# systems_pcb.net
KiCad netlist of a schematic drawn in Altium Designer
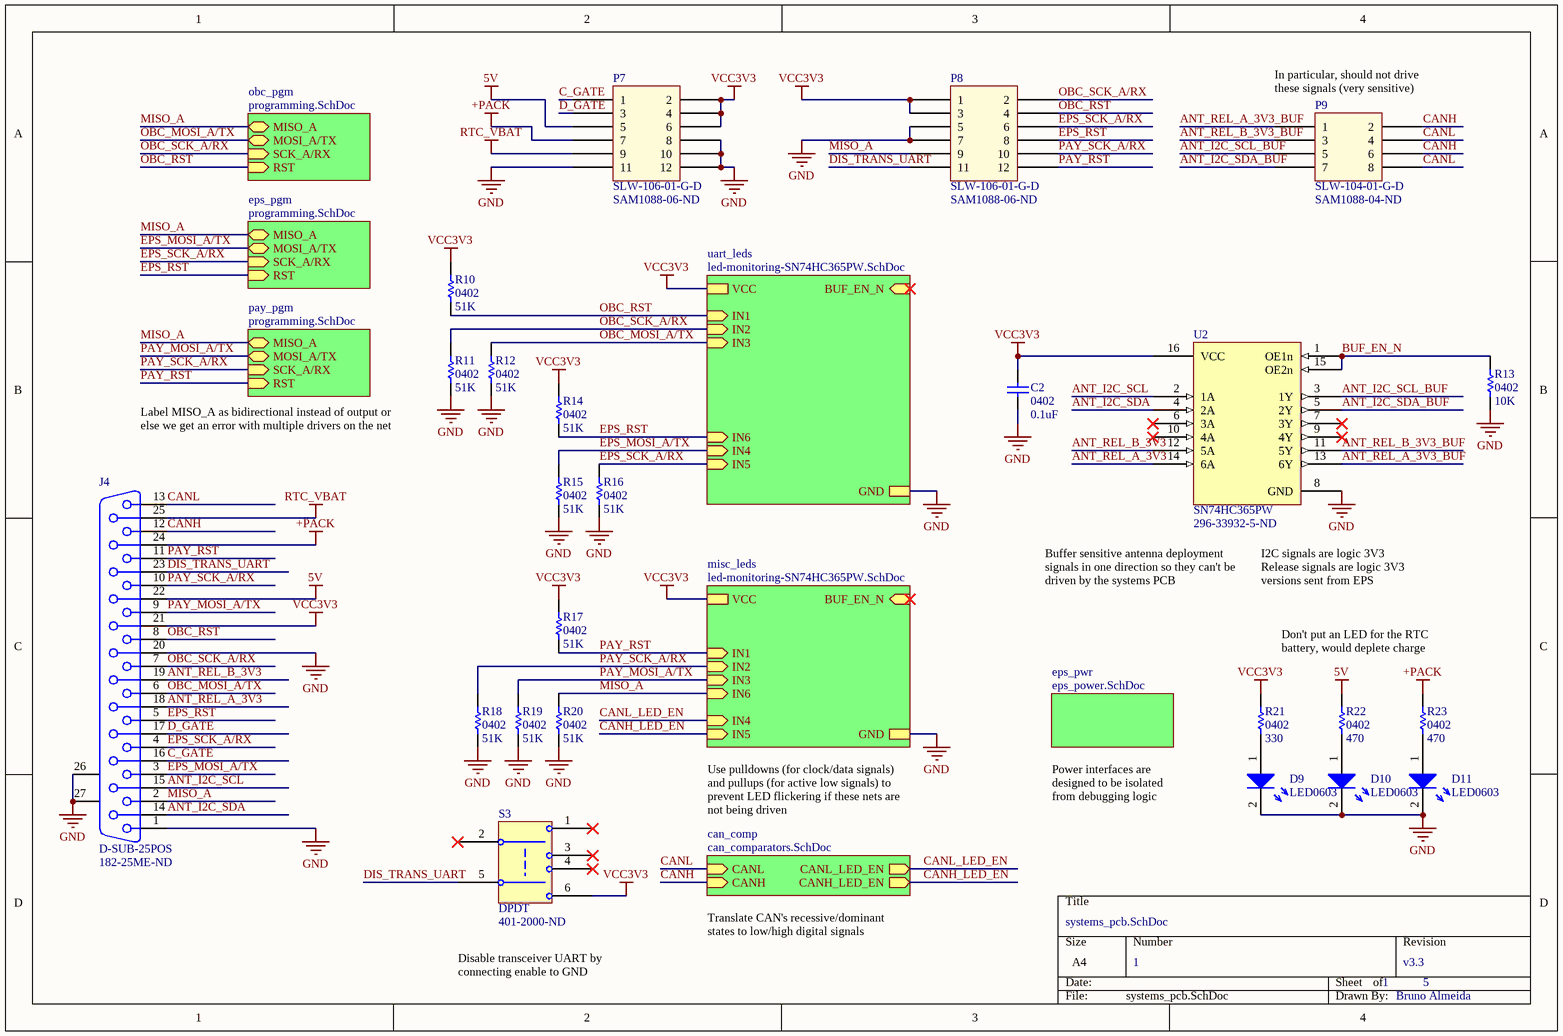
[diagram p0: systems_pcb.SchDoc]

(export (version "E")
  (design (tool "Eeschema 10.0.6"))
  (components
    (comp (ref "C2")
      (value "0402")
      (footprint "CAP0402R")
      (description "0402 capacitor")
      (fields
        (field (name "ALTIUM_VALUE") "0.1uF")
        (field (name "MANUFACTURER") "Taiyo Yuden")
        (field (name "MANUFACTURER PART NUMBER") "EMK105B7104KVHF")
      )
      (libsource (lib "heron-general") (part "CAP0402"))
    )
    (comp (ref "D9")
      (value "LED0603")
      (footprint "LED0603")
      (description "Generic 0603 LED. Use ChipLED from Osram for generic ones.")
      (libsource (lib "heron-general") (part "LED0603"))
    )
    (comp (ref "D10")
      (value "LED0603")
      (footprint "LED0603")
      (description "Generic 0603 LED. Use ChipLED from Osram for generic ones.")
      (libsource (lib "heron-general") (part "LED0603"))
    )
    (comp (ref "D11")
      (value "LED0603")
      (footprint "LED0603")
      (description "Generic 0603 LED. Use ChipLED from Osram for generic ones.")
      (libsource (lib "heron-general") (part "LED0603"))
    )
    (comp (ref "J4")
      (value "D-SUB-25POS")
      (footprint "D-SUB-25POS")
      (description "CONN D-SUB PLUG 25POS R/A SOLDER")
      (fields (field (name "SUPPLIER PART NUMBER 1") "182-25ME-ND"))
      (libsource (lib "heron-general") (part "D-SUB-25POS"))
    )
    (comp (ref "P7")
      (value "SLW-106-01-G-D")
      (footprint "SLW-106-01-X-D")
      (description "CONN RCPT 12POS 0.1 GOLD PCB")
      (fields (field (name "SUPPLIER PART NUMBER 1") "SAM1088-06-ND"))
      (libsource (lib "heron-general") (part "SLW-106-01-G-D"))
    )
    (comp (ref "P8")
      (value "SLW-106-01-G-D")
      (footprint "SLW-106-01-X-D")
      (description "CONN RCPT 12POS 0.1 GOLD PCB")
      (fields (field (name "SUPPLIER PART NUMBER 1") "SAM1088-06-ND"))
      (libsource (lib "heron-general") (part "SLW-106-01-G-D"))
    )
    (comp (ref "P9")
      (value "SLW-104-01-G-D")
      (footprint "SLW-104-01-X-D")
      (description "CONN RCPT 8POS 0.1 GOLD PCB")
      (fields (field (name "SUPPLIER PART NUMBER 1") "SAM1088-04-ND"))
      (libsource (lib "heron-general") (part "SLW-104-01-G-D"))
    )
    (comp (ref "R10")
      (value "0402")
      (footprint "RES0402R")
      (description "0402 resistor")
      (fields (field (name "ALTIUM_VALUE") "51K"))
      (libsource (lib "heron-general") (part "RES0402"))
    )
    (comp (ref "R11")
      (value "0402")
      (footprint "RES0402R")
      (description "0402 resistor")
      (fields (field (name "ALTIUM_VALUE") "51K"))
      (libsource (lib "heron-general") (part "RES0402"))
    )
    (comp (ref "R12")
      (value "0402")
      (footprint "RES0402R")
      (description "0402 resistor")
      (fields (field (name "ALTIUM_VALUE") "51K"))
      (libsource (lib "heron-general") (part "RES0402"))
    )
    (comp (ref "R13")
      (value "0402")
      (footprint "RES0402R")
      (description "0402 resistor")
      (fields
        (field (name "ALTIUM_VALUE") "10K")
        (field (name "MANUFACTURER") "Panasonic")
        (field (name "MANUFACTURER PART NUMBER") "ERJ-2RKF1002X")
      )
      (libsource (lib "heron-general") (part "RES0402"))
    )
    (comp (ref "R14")
      (value "0402")
      (footprint "RES0402R")
      (description "0402 resistor")
      (fields (field (name "ALTIUM_VALUE") "51K"))
      (libsource (lib "heron-general") (part "RES0402"))
    )
    (comp (ref "R15")
      (value "0402")
      (footprint "RES0402R")
      (description "0402 resistor")
      (fields (field (name "ALTIUM_VALUE") "51K"))
      (libsource (lib "heron-general") (part "RES0402"))
    )
    (comp (ref "R16")
      (value "0402")
      (footprint "RES0402R")
      (description "0402 resistor")
      (fields (field (name "ALTIUM_VALUE") "51K"))
      (libsource (lib "heron-general") (part "RES0402"))
    )
    (comp (ref "R17")
      (value "0402")
      (footprint "RES0402R")
      (description "0402 resistor")
      (fields (field (name "ALTIUM_VALUE") "51K"))
      (libsource (lib "heron-general") (part "RES0402"))
    )
    (comp (ref "R18")
      (value "0402")
      (footprint "RES0402R")
      (description "0402 resistor")
      (fields (field (name "ALTIUM_VALUE") "51K"))
      (libsource (lib "heron-general") (part "RES0402"))
    )
    (comp (ref "R19")
      (value "0402")
      (footprint "RES0402R")
      (description "0402 resistor")
      (fields (field (name "ALTIUM_VALUE") "51K"))
      (libsource (lib "heron-general") (part "RES0402"))
    )
    (comp (ref "R20")
      (value "0402")
      (footprint "RES0402R")
      (description "0402 resistor")
      (fields (field (name "ALTIUM_VALUE") "51K"))
      (libsource (lib "heron-general") (part "RES0402"))
    )
    (comp (ref "R21")
      (value "0402")
      (footprint "RES0402R")
      (description "0402 resistor")
      (fields (field (name "ALTIUM_VALUE") "330"))
      (libsource (lib "heron-general") (part "RES0402"))
    )
    (comp (ref "R22")
      (value "0402")
      (footprint "RES0402R")
      (description "0402 resistor")
      (fields (field (name "ALTIUM_VALUE") "470"))
      (libsource (lib "heron-general") (part "RES0402"))
    )
    (comp (ref "R23")
      (value "0402")
      (footprint "RES0402R")
      (description "0402 resistor")
      (fields (field (name "ALTIUM_VALUE") "470"))
      (libsource (lib "heron-general") (part "RES0402"))
    )
    (comp (ref "S3")
      (value "DPDT")
      (footprint "JS202011AQN - Slide Switch")
      (description "DPDT Switch, customized for the pinout of the JS202011AQN switch.")
      (fields (field (name "SUPPLIER PART NUMBER 1") "401-2000-ND"))
      (libsource (lib "heron-general") (part "DPDT Switch"))
    )
    (comp (ref "U2")
      (value "SN74HC365PW")
      (footprint "SOP65P640X120-16N")
      (description "Hex non-inverting buffer with 3-state outputs")
      (fields (field (name "SUPPLIER PART NUMBER 1") "296-33932-5-ND"))
      (libsource (lib "heron-general") (part "SN74HC365PW"))
    )
  )
  (nets
    (net (code "1") (name "+PACK") (class "Default")
      (node (ref "J4") (pin "24") (pinfunction "24_24") (pintype "passive"))
      (node (ref "P7") (pin "7") (pinfunction "7_7") (pintype "passive"))
      (node (ref "R23") (pin "2") (pinfunction "2_2") (pintype "passive"))
    )
    (net (code "2") (name "/ANT_I2C_SCL") (class "Default")
      (node (ref "J4") (pin "15") (pinfunction "15_15") (pintype "passive"))
      (node (ref "U2") (pin "2") (pinfunction "1A_2") (pintype "input"))
    )
    (net (code "3") (name "/ANT_I2C_SCL_BUF") (class "Default")
      (node (ref "P9") (pin "5") (pinfunction "5_5") (pintype "passive"))
      (node (ref "U2") (pin "3") (pinfunction "1Y_3") (pintype "output"))
    )
    (net (code "4") (name "/ANT_I2C_SDA") (class "Default")
      (node (ref "J4") (pin "14") (pinfunction "14_14") (pintype "passive"))
      (node (ref "U2") (pin "4") (pinfunction "2A_4") (pintype "input"))
    )
    (net (code "5") (name "/ANT_I2C_SDA_BUF") (class "Default")
      (node (ref "P9") (pin "7") (pinfunction "7_7") (pintype "passive"))
      (node (ref "U2") (pin "5") (pinfunction "2Y_5") (pintype "output"))
    )
    (net (code "6") (name "/ANT_REL_A_3V3") (class "Default")
      (node (ref "J4") (pin "18") (pinfunction "18_18") (pintype "passive"))
      (node (ref "U2") (pin "14") (pinfunction "6A_14") (pintype "input"))
    )
    (net (code "7") (name "/ANT_REL_A_3V3_BUF") (class "Default")
      (node (ref "P9") (pin "1") (pinfunction "1_1") (pintype "passive"))
      (node (ref "U2") (pin "13") (pinfunction "6Y_13") (pintype "output"))
    )
    (net (code "8") (name "/ANT_REL_B_3V3") (class "Default")
      (node (ref "J4") (pin "19") (pinfunction "19_19") (pintype "passive"))
      (node (ref "U2") (pin "12") (pinfunction "5A_12") (pintype "input"))
    )
    (net (code "9") (name "/ANT_REL_B_3V3_BUF") (class "Default")
      (node (ref "P9") (pin "3") (pinfunction "3_3") (pintype "passive"))
      (node (ref "U2") (pin "11") (pinfunction "5Y_11") (pintype "output"))
    )
    (net (code "10") (name "/BUF_EN_N") (class "Default")
      (node (ref "R13") (pin "2") (pinfunction "2_2") (pintype "passive"))
      (node (ref "U2") (pin "1") (pinfunction "OE1n_1") (pintype "input"))
      (node (ref "U2") (pin "15") (pinfunction "OE2n_15") (pintype "input"))
    )
    (net (code "13") (name "/CANH") (class "Default")
      (node (ref "J4") (pin "12") (pinfunction "12_12") (pintype "passive"))
      (node (ref "P9") (pin "2") (pinfunction "2_2") (pintype "passive"))
      (node (ref "P9") (pin "6") (pinfunction "6_6") (pintype "passive"))
    )
    (net (code "15") (name "/CANL") (class "Default")
      (node (ref "J4") (pin "13") (pinfunction "13_13") (pintype "passive"))
      (node (ref "P9") (pin "4") (pinfunction "4_4") (pintype "passive"))
      (node (ref "P9") (pin "8") (pinfunction "8_8") (pintype "passive"))
    )
    (net (code "17") (name "/C_GATE") (class "Default")
      (node (ref "J4") (pin "16") (pinfunction "16_16") (pintype "passive"))
      (node (ref "P7") (pin "1") (pinfunction "1_1") (pintype "passive"))
    )
    (net (code "18") (name "/DIS_TRANS_UART") (class "Default")
      (node (ref "J4") (pin "23") (pinfunction "23_23") (pintype "passive"))
      (node (ref "P8") (pin "11") (pinfunction "11_11") (pintype "passive"))
      (node (ref "S3") (pin "5") (pinfunction "POLE2_5") (pintype "passive"))
    )
    (net (code "19") (name "/D_GATE") (class "Default")
      (node (ref "J4") (pin "17") (pinfunction "17_17") (pintype "passive"))
      (node (ref "P7") (pin "3") (pinfunction "3_3") (pintype "passive"))
    )
    (net (code "20") (name "/EPS_MOSI_A{slash}TX") (class "Default")
      (node (ref "J4") (pin "3") (pinfunction "3_3") (pintype "passive"))
      (node (ref "R15") (pin "2") (pinfunction "2_2") (pintype "passive"))
    )
    (net (code "21") (name "/EPS_RST") (class "Default")
      (node (ref "J4") (pin "5") (pinfunction "5_5") (pintype "passive"))
      (node (ref "P8") (pin "8") (pinfunction "8_8") (pintype "passive"))
      (node (ref "R14") (pin "1") (pinfunction "1_1") (pintype "passive"))
    )
    (net (code "22") (name "/EPS_SCK_A{slash}RX") (class "Default")
      (node (ref "J4") (pin "4") (pinfunction "4_4") (pintype "passive"))
      (node (ref "P8") (pin "6") (pinfunction "6_6") (pintype "passive"))
      (node (ref "R16") (pin "2") (pinfunction "2_2") (pintype "passive"))
    )
    (net (code "23") (name "/MISO_A") (class "Default")
      (node (ref "J4") (pin "2") (pinfunction "2_2") (pintype "passive"))
      (node (ref "P8") (pin "9") (pinfunction "9_9") (pintype "passive"))
      (node (ref "R20") (pin "2") (pinfunction "2_2") (pintype "passive"))
    )
    (net (code "24") (name "/OBC_MOSI_A{slash}TX") (class "Default")
      (node (ref "J4") (pin "6") (pinfunction "6_6") (pintype "passive"))
      (node (ref "R12") (pin "2") (pinfunction "2_2") (pintype "passive"))
    )
    (net (code "25") (name "/OBC_RST") (class "Default")
      (node (ref "J4") (pin "8") (pinfunction "8_8") (pintype "passive"))
      (node (ref "P8") (pin "4") (pinfunction "4_4") (pintype "passive"))
      (node (ref "R10") (pin "1") (pinfunction "1_1") (pintype "passive"))
    )
    (net (code "26") (name "/OBC_SCK_A{slash}RX") (class "Default")
      (node (ref "J4") (pin "7") (pinfunction "7_7") (pintype "passive"))
      (node (ref "P8") (pin "2") (pinfunction "2_2") (pintype "passive"))
      (node (ref "R11") (pin "2") (pinfunction "2_2") (pintype "passive"))
    )
    (net (code "27") (name "/PAY_MOSI_A{slash}TX") (class "Default")
      (node (ref "J4") (pin "9") (pinfunction "9_9") (pintype "passive"))
      (node (ref "R19") (pin "2") (pinfunction "2_2") (pintype "passive"))
    )
    (net (code "28") (name "/PAY_RST") (class "Default")
      (node (ref "J4") (pin "11") (pinfunction "11_11") (pintype "passive"))
      (node (ref "P8") (pin "12") (pinfunction "12_12") (pintype "passive"))
      (node (ref "R17") (pin "1") (pinfunction "1_1") (pintype "passive"))
    )
    (net (code "29") (name "/PAY_SCK_A{slash}RX") (class "Default")
      (node (ref "J4") (pin "10") (pinfunction "10_10") (pintype "passive"))
      (node (ref "P8") (pin "10") (pinfunction "10_10") (pintype "passive"))
      (node (ref "R18") (pin "2") (pinfunction "2_2") (pintype "passive"))
    )
    (net (code "30") (name "5V") (class "Default")
      (node (ref "J4") (pin "22") (pinfunction "22_22") (pintype "passive"))
      (node (ref "P7") (pin "5") (pinfunction "5_5") (pintype "passive"))
      (node (ref "R22") (pin "2") (pinfunction "2_2") (pintype "passive"))
    )
    (net (code "31") (name "GND") (class "Default")
      (node (ref "C2") (pin "1") (pinfunction "1_1") (pintype "passive"))
      (node (ref "D10") (pin "2") (pinfunction "2_2") (pintype "passive"))
      (node (ref "D11") (pin "2") (pinfunction "2_2") (pintype "passive"))
      (node (ref "D9") (pin "2") (pinfunction "2_2") (pintype "passive"))
      (node (ref "J4") (pin "1") (pinfunction "1_1") (pintype "passive"))
      (node (ref "J4") (pin "20") (pinfunction "20_20") (pintype "passive"))
      (node (ref "J4") (pin "26") (pinfunction "MH1_26") (pintype "passive"))
      (node (ref "J4") (pin "27") (pinfunction "MH2_27") (pintype "passive"))
      (node (ref "P7") (pin "10") (pinfunction "10_10") (pintype "passive"))
      (node (ref "P7") (pin "11") (pinfunction "11_11") (pintype "passive"))
      (node (ref "P7") (pin "12") (pinfunction "12_12") (pintype "passive"))
      (node (ref "P7") (pin "8") (pinfunction "8_8") (pintype "passive"))
      (node (ref "P8") (pin "5") (pinfunction "5_5") (pintype "passive"))
      (node (ref "P8") (pin "7") (pinfunction "7_7") (pintype "passive"))
      (node (ref "R11") (pin "1") (pinfunction "1_1") (pintype "passive"))
      (node (ref "R12") (pin "1") (pinfunction "1_1") (pintype "passive"))
      (node (ref "R13") (pin "1") (pinfunction "1_1") (pintype "passive"))
      (node (ref "R15") (pin "1") (pinfunction "1_1") (pintype "passive"))
      (node (ref "R16") (pin "1") (pinfunction "1_1") (pintype "passive"))
      (node (ref "R18") (pin "1") (pinfunction "1_1") (pintype "passive"))
      (node (ref "R19") (pin "1") (pinfunction "1_1") (pintype "passive"))
      (node (ref "R20") (pin "1") (pinfunction "1_1") (pintype "passive"))
      (node (ref "U2") (pin "8") (pinfunction "GND_8") (pintype "power_in"))
    )
    (net (code "32") (name "Net-(D9-Pad1)") (class "Default")
      (node (ref "D9") (pin "1") (pinfunction "1_1") (pintype "passive"))
      (node (ref "R21") (pin "1") (pinfunction "1_1") (pintype "passive"))
    )
    (net (code "33") (name "Net-(D10-Pad1)") (class "Default")
      (node (ref "D10") (pin "1") (pinfunction "1_1") (pintype "passive"))
      (node (ref "R22") (pin "1") (pinfunction "1_1") (pintype "passive"))
    )
    (net (code "34") (name "Net-(D11-Pad1)") (class "Default")
      (node (ref "D11") (pin "1") (pinfunction "1_1") (pintype "passive"))
      (node (ref "R23") (pin "1") (pinfunction "1_1") (pintype "passive"))
    )
    (net (code "35") (name "RTC_VBAT") (class "Default")
      (node (ref "J4") (pin "25") (pinfunction "25_25") (pintype "passive"))
      (node (ref "P7") (pin "9") (pinfunction "9_9") (pintype "passive"))
    )
    (net (code "36") (name "VCC3V3") (class "Default")
      (node (ref "C2") (pin "2") (pinfunction "2_2") (pintype "passive"))
      (node (ref "J4") (pin "21") (pinfunction "21_21") (pintype "passive"))
      (node (ref "P7") (pin "2") (pinfunction "2_2") (pintype "passive"))
      (node (ref "P7") (pin "4") (pinfunction "4_4") (pintype "passive"))
      (node (ref "P7") (pin "6") (pinfunction "6_6") (pintype "passive"))
      (node (ref "P8") (pin "1") (pinfunction "1_1") (pintype "passive"))
      (node (ref "P8") (pin "3") (pinfunction "3_3") (pintype "passive"))
      (node (ref "R10") (pin "2") (pinfunction "2_2") (pintype "passive"))
      (node (ref "R14") (pin "2") (pinfunction "2_2") (pintype "passive"))
      (node (ref "R17") (pin "2") (pinfunction "2_2") (pintype "passive"))
      (node (ref "R21") (pin "2") (pinfunction "2_2") (pintype "passive"))
      (node (ref "S3") (pin "6") (pinfunction "POLE2B_6") (pintype "passive"))
      (node (ref "U2") (pin "16") (pinfunction "VCC_16") (pintype "power_in"))
    )
    (net (code "37") (name "unconnected-(S3-POLE1-Pad2)") (class "Default")
      (node (ref "S3") (pin "2") (pinfunction "POLE1_2") (pintype "passive+no_connect"))
    )
    (net (code "38") (name "unconnected-(S3-POLE1A-Pad1)") (class "Default")
      (node (ref "S3") (pin "1") (pinfunction "POLE1A_1") (pintype "passive+no_connect"))
    )
    (net (code "39") (name "unconnected-(S3-POLE1B-Pad3)") (class "Default")
      (node (ref "S3") (pin "3") (pinfunction "POLE1B_3") (pintype "passive+no_connect"))
    )
    (net (code "40") (name "unconnected-(S3-POLE2A-Pad4)") (class "Default")
      (node (ref "S3") (pin "4") (pinfunction "POLE2A_4") (pintype "passive+no_connect"))
    )
    (net (code "41") (name "unconnected-(U2-3A-Pad6)") (class "Default")
      (node (ref "U2") (pin "6") (pinfunction "3A_6") (pintype "input+no_connect"))
    )
    (net (code "42") (name "unconnected-(U2-3Y-Pad7)") (class "Default")
      (node (ref "U2") (pin "7") (pinfunction "3Y_7") (pintype "output+no_connect"))
    )
    (net (code "43") (name "unconnected-(U2-4A-Pad10)") (class "Default")
      (node (ref "U2") (pin "10") (pinfunction "4A_10") (pintype "input+no_connect"))
    )
    (net (code "44") (name "unconnected-(U2-4Y-Pad9)") (class "Default")
      (node (ref "U2") (pin "9") (pinfunction "4Y_9") (pintype "output+no_connect"))
    )
  )
)
